# driver.net
KiCad netlist of a schematic drawn in Altium Designer
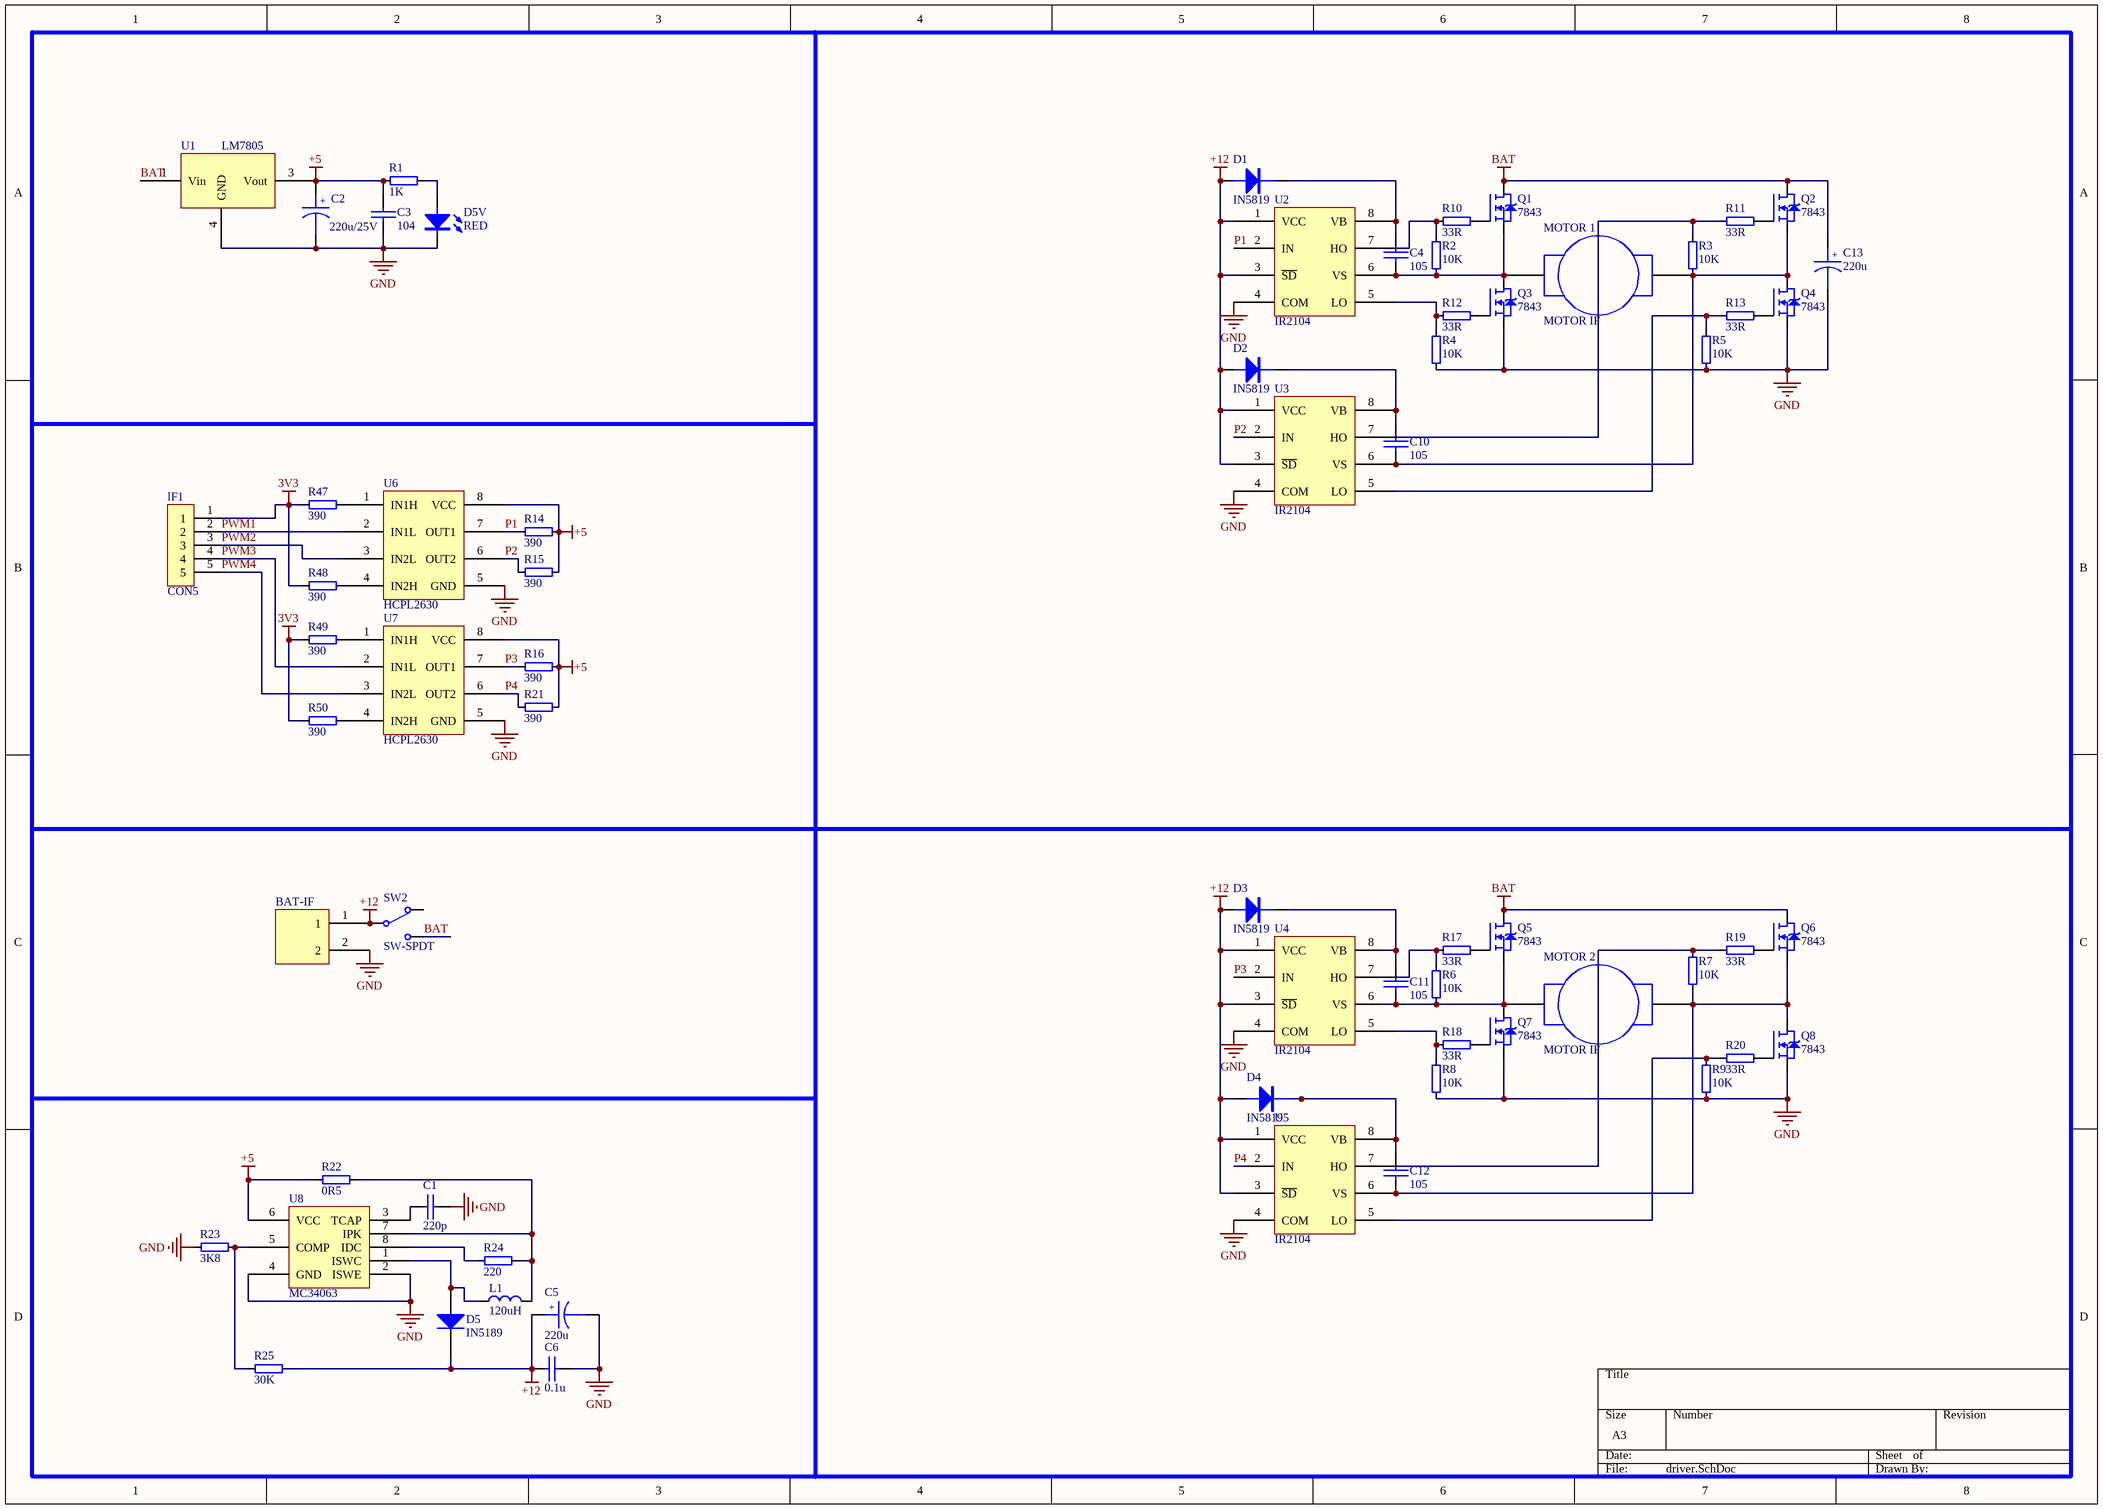
[diagram p0: driver.SchDoc]

(export (version "E")
  (design (tool "Eeschema 10.0.6"))
  (components
    (comp (ref "B1") (value "BAT-IF") (footprint "KF301-2P") (libsource (lib "General") (part "BAT-IF")))
    (comp (ref "C1")
      (value "220p")
      (footprint "0603")
      (description "Capacitor")
      (libsource (lib "电容") (part "普通电容"))
    )
    (comp (ref "C2")
      (value "220u/25V")
      (footprint "CAP 2.5*6.3*7 - BK")
      (description "Capacitor")
      (libsource (lib "电容") (part "电解电容"))
    )
    (comp (ref "C3")
      (value "104")
      (footprint "0603")
      (description "Capacitor")
      (libsource (lib "电容") (part "普通电容"))
    )
    (comp (ref "C4")
      (value "105")
      (footprint "0603")
      (description "Capacitor")
      (libsource (lib "电容") (part "普通电容"))
    )
    (comp (ref "C5")
      (value "220u")
      (footprint "CAP 2.5*6.3*7 - BK")
      (description "Capacitor")
      (libsource (lib "电容") (part "电解电容"))
    )
    (comp (ref "C6")
      (value "0.1u")
      (footprint "0603")
      (description "Capacitor")
      (libsource (lib "电容") (part "普通电容"))
    )
    (comp (ref "C10")
      (value "105")
      (footprint "0603")
      (description "Capacitor")
      (libsource (lib "电容") (part "普通电容"))
    )
    (comp (ref "C11")
      (value "105")
      (footprint "0603")
      (description "Capacitor")
      (libsource (lib "电容") (part "普通电容"))
    )
    (comp (ref "C12")
      (value "105")
      (footprint "0603")
      (description "Capacitor")
      (libsource (lib "电容") (part "普通电容"))
    )
    (comp (ref "C13")
      (value "220u")
      (footprint "CAP 2.5*6.3*7 - BK")
      (description "Capacitor")
      (libsource (lib "电容") (part "电解电容"))
    )
    (comp (ref "D1") (value "IN5819") (footprint "SOD-123") (libsource (lib "常用1") (part "DIODE")))
    (comp (ref "D2") (value "IN5819") (footprint "SOD-123") (libsource (lib "常用1") (part "DIODE")))
    (comp (ref "D3") (value "IN5819") (footprint "SOD-123") (libsource (lib "常用1") (part "DIODE")))
    (comp (ref "D4") (value "IN5819") (footprint "SOD-123") (libsource (lib "常用1") (part "DIODE")))
    (comp (ref "D5")
      (value "IN5189")
      (footprint "SMA")
      (description "SS14")
      (fields (field (name "PUBLISHER") "Altium Limited"))
      (libsource (lib "Miscellaneous Devices") (part "Diode 1N5400"))
    )
    (comp (ref "D5V")
      (value "RED")
      (footprint "LED-0603")
      (description "LED")
      (libsource (lib "General") (part "LED"))
    )
    (comp (ref "L1")
      (value "120uH")
      (footprint "L1210")
      (description "Inductance")
      (libsource (lib "General") (part "INDUCTANCE"))
    )
    (comp (ref "lF1") (value "CON5") (footprint "2.54排针1X5") (libsource (lib "常用元件库") (part "CON5")))
    (comp (ref "MOTOR 1")
      (value "MOTOR IF")
      (footprint "KF301-2P")
      (libsource (lib "General") (part "MOTOR IF"))
    )
    (comp (ref "MOTOR 2")
      (value "MOTOR IF")
      (footprint "KF301-2P")
      (libsource (lib "General") (part "MOTOR IF"))
    )
    (comp (ref "Q1")
      (value "7843")
      (footprint "TO-252")
      (description "N-Channel MOSFET")
      (libsource (lib "General") (part "FDB52N20_2"))
    )
    (comp (ref "Q2")
      (value "7843")
      (footprint "TO-252")
      (description "N-Channel MOSFET")
      (libsource (lib "General") (part "FDB52N20_2"))
    )
    (comp (ref "Q3")
      (value "7843")
      (footprint "TO-252")
      (description "N-Channel MOSFET")
      (libsource (lib "General") (part "FDB52N20_2"))
    )
    (comp (ref "Q4")
      (value "7843")
      (footprint "TO-252")
      (description "N-Channel MOSFET")
      (libsource (lib "General") (part "FDB52N20_2"))
    )
    (comp (ref "Q5")
      (value "7843")
      (footprint "TO-252")
      (description "N-Channel MOSFET")
      (libsource (lib "General") (part "FDB52N20_2"))
    )
    (comp (ref "Q6")
      (value "7843")
      (footprint "TO-252")
      (description "N-Channel MOSFET")
      (libsource (lib "General") (part "FDB52N20_2"))
    )
    (comp (ref "Q7")
      (value "7843")
      (footprint "TO-252")
      (description "N-Channel MOSFET")
      (libsource (lib "General") (part "FDB52N20_2"))
    )
    (comp (ref "Q8")
      (value "7843")
      (footprint "TO-252")
      (description "N-Channel MOSFET")
      (libsource (lib "General") (part "FDB52N20_2"))
    )
    (comp (ref "R1") (value "1K") (footprint "0603") (libsource (lib "电阻") (part "RES")))
    (comp (ref "R2") (value "10K") (footprint "0603") (libsource (lib "电阻") (part "RES")))
    (comp (ref "R3") (value "10K") (footprint "0603") (libsource (lib "电阻") (part "RES")))
    (comp (ref "R4") (value "10K") (footprint "0603") (libsource (lib "电阻") (part "RES")))
    (comp (ref "R5") (value "10K") (footprint "0603") (libsource (lib "电阻") (part "RES")))
    (comp (ref "R6") (value "10K") (footprint "0603") (libsource (lib "电阻") (part "RES")))
    (comp (ref "R7") (value "10K") (footprint "0603") (libsource (lib "电阻") (part "RES")))
    (comp (ref "R8") (value "10K") (footprint "0603") (libsource (lib "电阻") (part "RES")))
    (comp (ref "R9") (value "10K") (footprint "0603") (libsource (lib "电阻") (part "RES")))
    (comp (ref "R10") (value "33R") (footprint "0603") (libsource (lib "电阻") (part "RES")))
    (comp (ref "R11") (value "33R") (footprint "0603") (libsource (lib "电阻") (part "RES")))
    (comp (ref "R12") (value "33R") (footprint "0603") (libsource (lib "电阻") (part "RES")))
    (comp (ref "R13") (value "33R") (footprint "0603") (libsource (lib "电阻") (part "RES")))
    (comp (ref "R14") (value "390") (footprint "0603") (libsource (lib "电阻") (part "RES")))
    (comp (ref "R15") (value "390") (footprint "0603") (libsource (lib "电阻") (part "RES")))
    (comp (ref "R16") (value "390") (footprint "0603") (libsource (lib "电阻") (part "RES")))
    (comp (ref "R17") (value "33R") (footprint "0603") (libsource (lib "电阻") (part "RES")))
    (comp (ref "R18") (value "33R") (footprint "0603") (libsource (lib "电阻") (part "RES")))
    (comp (ref "R19") (value "33R") (footprint "0603") (libsource (lib "电阻") (part "RES")))
    (comp (ref "R20") (value "33R") (footprint "0603") (libsource (lib "电阻") (part "RES")))
    (comp (ref "R21") (value "390") (footprint "0603") (libsource (lib "电阻") (part "RES")))
    (comp (ref "R22") (value "0R5") (footprint "0603") (libsource (lib "电阻") (part "RES")))
    (comp (ref "R23") (value "3K8") (footprint "0603") (libsource (lib "电阻") (part "RES")))
    (comp (ref "R24") (value "220") (footprint "0603") (libsource (lib "电阻") (part "RES")))
    (comp (ref "R25") (value "30K") (footprint "0603") (libsource (lib "电阻") (part "RES")))
    (comp (ref "R47") (value "390") (footprint "0603") (libsource (lib "电阻") (part "RES")))
    (comp (ref "R48") (value "390") (footprint "0603") (libsource (lib "电阻") (part "RES")))
    (comp (ref "R49") (value "390") (footprint "0603") (libsource (lib "电阻") (part "RES")))
    (comp (ref "R50") (value "390") (footprint "0603") (libsource (lib "电阻") (part "RES")))
    (comp (ref "SW2")
      (value "SW-SPDT")
      (footprint "SW3-H2X3_8.6X4.5_L")
      (description "Switch")
      (libsource (lib "General") (part "SWITCH-NKK-M201x"))
    )
    (comp (ref "U1") (value "LM7805") (footprint "TO-252") (libsource (lib "电源") (part "7805")))
    (comp (ref "U2") (value "IR2104") (footprint "SO8_M") (libsource (lib "General") (part "IR2104")))
    (comp (ref "U3") (value "IR2104") (footprint "SO8_M") (libsource (lib "General") (part "IR2104")))
    (comp (ref "U4") (value "IR2104") (footprint "SO8_M") (libsource (lib "General") (part "IR2104")))
    (comp (ref "U5") (value "IR2104") (footprint "SO8_M") (libsource (lib "General") (part "IR2104")))
    (comp (ref "U6") (value "HCPL2630") (footprint "DIP-8") (libsource (lib "常用元件库") (part "HCPL2630")))
    (comp (ref "U7") (value "HCPL2630") (footprint "DIP-8") (libsource (lib "常用元件库") (part "HCPL2630")))
    (comp (ref "U8") (value "MC34063") (footprint "SO-8") (libsource (lib "PCB_Project") (part "MC34063")))
  )
  (nets
    (net (code "1") (name "+5") (class "Default")
      (node (ref "C2") (pin "1") (pinfunction "1_1") (pintype "passive"))
      (node (ref "C3") (pin "1") (pinfunction "1_1") (pintype "passive"))
      (node (ref "R1") (pin "1") (pinfunction "1_1") (pintype "passive"))
      (node (ref "R14") (pin "1") (pinfunction "1_1") (pintype "passive"))
      (node (ref "R15") (pin "1") (pinfunction "1_1") (pintype "passive"))
      (node (ref "R16") (pin "2") (pinfunction "2_2") (pintype "passive"))
      (node (ref "R21") (pin "1") (pinfunction "1_1") (pintype "passive"))
      (node (ref "R22") (pin "1") (pinfunction "1_1") (pintype "passive"))
      (node (ref "U1") (pin "3") (pinfunction "Vout_3") (pintype "passive"))
      (node (ref "U6") (pin "8") (pinfunction "VCC_8") (pintype "passive"))
      (node (ref "U7") (pin "8") (pinfunction "VCC_8") (pintype "passive"))
      (node (ref "U8") (pin "6") (pinfunction "VCC_6") (pintype "passive"))
    )
    (net (code "2") (name "+12") (class "Default")
      (node (ref "B1") (pin "1") (pinfunction "1_1") (pintype "passive"))
      (node (ref "C5") (pin "1") (pinfunction "1_1") (pintype "passive"))
      (node (ref "C6") (pin "1") (pinfunction "1_1") (pintype "passive"))
      (node (ref "D1") (pin "1") (pintype "passive"))
      (node (ref "D2") (pin "1") (pintype "passive"))
      (node (ref "D3") (pin "1") (pintype "passive"))
      (node (ref "D4") (pin "1") (pintype "passive"))
      (node (ref "D5") (pin "2") (pinfunction "K_2") (pintype "passive"))
      (node (ref "R25") (pin "2") (pinfunction "2_2") (pintype "passive"))
      (node (ref "SW2") (pin "2") (pinfunction "2_2") (pintype "passive"))
      (node (ref "U2") (pin "1") (pinfunction "VCC_1") (pintype "passive"))
      (node (ref "U2") (pin "3") (pinfunction "~{SD}_3") (pintype "passive"))
      (node (ref "U3") (pin "1") (pinfunction "VCC_1") (pintype "passive"))
      (node (ref "U3") (pin "3") (pinfunction "~{SD}_3") (pintype "passive"))
      (node (ref "U4") (pin "1") (pinfunction "VCC_1") (pintype "passive"))
      (node (ref "U4") (pin "3") (pinfunction "~{SD}_3") (pintype "passive"))
      (node (ref "U5") (pin "1") (pinfunction "VCC_1") (pintype "passive"))
      (node (ref "U5") (pin "3") (pinfunction "~{SD}_3") (pintype "passive"))
    )
    (net (code "3") (name "/P1") (class "Default")
      (node (ref "R14") (pin "2") (pinfunction "2_2") (pintype "passive"))
      (node (ref "U2") (pin "2") (pinfunction "IN_2") (pintype "passive"))
      (node (ref "U6") (pin "7") (pinfunction "OUT1_7") (pintype "passive"))
    )
    (net (code "4") (name "/P2") (class "Default")
      (node (ref "R15") (pin "2") (pinfunction "2_2") (pintype "passive"))
      (node (ref "U3") (pin "2") (pinfunction "IN_2") (pintype "passive"))
      (node (ref "U6") (pin "6") (pinfunction "OUT2_6") (pintype "passive"))
    )
    (net (code "5") (name "/P3") (class "Default")
      (node (ref "R16") (pin "1") (pinfunction "1_1") (pintype "passive"))
      (node (ref "U4") (pin "2") (pinfunction "IN_2") (pintype "passive"))
      (node (ref "U7") (pin "7") (pinfunction "OUT1_7") (pintype "passive"))
    )
    (net (code "6") (name "/P4") (class "Default")
      (node (ref "R21") (pin "2") (pinfunction "2_2") (pintype "passive"))
      (node (ref "U5") (pin "2") (pinfunction "IN_2") (pintype "passive"))
      (node (ref "U7") (pin "6") (pinfunction "OUT2_6") (pintype "passive"))
    )
    (net (code "7") (name "/PWM1") (class "Default")
      (node (ref "U6") (pin "2") (pinfunction "IN1L_2") (pintype "passive"))
      (node (ref "lF1") (pin "2") (pinfunction "2_2") (pintype "passive"))
    )
    (net (code "8") (name "/PWM2") (class "Default")
      (node (ref "U6") (pin "3") (pinfunction "IN2L_3") (pintype "passive"))
      (node (ref "lF1") (pin "3") (pinfunction "3_3") (pintype "passive"))
    )
    (net (code "9") (name "/PWM3") (class "Default")
      (node (ref "U7") (pin "2") (pinfunction "IN1L_2") (pintype "passive"))
      (node (ref "lF1") (pin "4") (pinfunction "4_4") (pintype "passive"))
    )
    (net (code "10") (name "/PWM4") (class "Default")
      (node (ref "U7") (pin "3") (pinfunction "IN2L_3") (pintype "passive"))
      (node (ref "lF1") (pin "5") (pinfunction "5_5") (pintype "passive"))
    )
    (net (code "11") (name "3V3") (class "Default")
      (node (ref "R47") (pin "1") (pinfunction "1_1") (pintype "passive"))
      (node (ref "R48") (pin "1") (pinfunction "1_1") (pintype "passive"))
      (node (ref "R49") (pin "1") (pinfunction "1_1") (pintype "passive"))
      (node (ref "R50") (pin "1") (pinfunction "1_1") (pintype "passive"))
      (node (ref "lF1") (pin "1") (pinfunction "1_1") (pintype "passive"))
    )
    (net (code "12") (name "BAT") (class "Default")
      (node (ref "C13") (pin "1") (pinfunction "1_1") (pintype "passive"))
      (node (ref "Q1") (pin "4") (pinfunction "D_4") (pintype "passive"))
      (node (ref "Q2") (pin "4") (pinfunction "D_4") (pintype "passive"))
      (node (ref "Q5") (pin "4") (pinfunction "D_4") (pintype "passive"))
      (node (ref "Q6") (pin "4") (pinfunction "D_4") (pintype "passive"))
      (node (ref "SW2") (pin "3") (pinfunction "3_3") (pintype "passive"))
      (node (ref "U1") (pin "1") (pinfunction "Vin_1") (pintype "passive"))
    )
    (net (code "13") (name "GND") (class "Default")
      (node (ref "B1") (pin "2") (pinfunction "2_2") (pintype "passive"))
      (node (ref "C1") (pin "2") (pinfunction "2_2") (pintype "passive"))
      (node (ref "C13") (pin "2") (pinfunction "2_2") (pintype "passive"))
      (node (ref "C2") (pin "2") (pinfunction "2_2") (pintype "passive"))
      (node (ref "C3") (pin "2") (pinfunction "2_2") (pintype "passive"))
      (node (ref "C5") (pin "2") (pinfunction "2_2") (pintype "passive"))
      (node (ref "C6") (pin "2") (pinfunction "2_2") (pintype "passive"))
      (node (ref "D5V") (pin "2") (pinfunction "C_2") (pintype "passive"))
      (node (ref "Q3") (pin "3") (pinfunction "S_3") (pintype "passive"))
      (node (ref "Q4") (pin "3") (pinfunction "S_3") (pintype "passive"))
      (node (ref "Q7") (pin "3") (pinfunction "S_3") (pintype "passive"))
      (node (ref "Q8") (pin "3") (pinfunction "S_3") (pintype "passive"))
      (node (ref "R23") (pin "1") (pinfunction "1_1") (pintype "passive"))
      (node (ref "R4") (pin "1") (pinfunction "1_1") (pintype "passive"))
      (node (ref "R5") (pin "1") (pinfunction "1_1") (pintype "passive"))
      (node (ref "R8") (pin "1") (pinfunction "1_1") (pintype "passive"))
      (node (ref "R9") (pin "1") (pinfunction "1_1") (pintype "passive"))
      (node (ref "U1") (pin "4") (pinfunction "GND_4") (pintype "passive"))
      (node (ref "U2") (pin "4") (pinfunction "COM_4") (pintype "passive"))
      (node (ref "U3") (pin "4") (pinfunction "COM_4") (pintype "passive"))
      (node (ref "U4") (pin "4") (pinfunction "COM_4") (pintype "passive"))
      (node (ref "U5") (pin "4") (pinfunction "COM_4") (pintype "passive"))
      (node (ref "U6") (pin "5") (pinfunction "GND_5") (pintype "passive"))
      (node (ref "U7") (pin "5") (pinfunction "GND_5") (pintype "passive"))
      (node (ref "U8") (pin "2") (pinfunction "ISWE_2") (pintype "passive"))
      (node (ref "U8") (pin "4") (pinfunction "GND_4") (pintype "passive"))
    )
    (net (code "14") (name "Net-(D5-A)") (class "Default")
      (node (ref "D5") (pin "1") (pinfunction "A_1") (pintype "passive"))
      (node (ref "L1") (pin "1") (pinfunction "1_1") (pintype "passive"))
      (node (ref "U8") (pin "1") (pinfunction "ISWC_1") (pintype "passive"))
    )
    (net (code "15") (name "Net-(D5V-A)") (class "Default")
      (node (ref "D5V") (pin "1") (pinfunction "A_1") (pintype "passive"))
      (node (ref "R1") (pin "2") (pinfunction "2_2") (pintype "passive"))
    )
    (net (code "16") (name "Net-(Q1-G)") (class "Default")
      (node (ref "Q1") (pin "1") (pinfunction "G_1") (pintype "passive"))
      (node (ref "R10") (pin "2") (pinfunction "2_2") (pintype "passive"))
    )
    (net (code "17") (name "Net-(Q1-S)") (class "Default")
      (node (ref "C4") (pin "2") (pinfunction "2_2") (pintype "passive"))
      (node (ref "MOTOR 1") (pin "2") (pinfunction "2_2") (pintype "passive"))
      (node (ref "Q1") (pin "3") (pinfunction "S_3") (pintype "passive"))
      (node (ref "Q3") (pin "4") (pinfunction "D_4") (pintype "passive"))
      (node (ref "R2") (pin "1") (pinfunction "1_1") (pintype "passive"))
      (node (ref "U2") (pin "6") (pinfunction "VS_6") (pintype "passive"))
    )
    (net (code "18") (name "Net-(Q2-G)") (class "Default")
      (node (ref "Q2") (pin "1") (pinfunction "G_1") (pintype "passive"))
      (node (ref "R11") (pin "2") (pinfunction "2_2") (pintype "passive"))
    )
    (net (code "19") (name "Net-(Q2-S)") (class "Default")
      (node (ref "C10") (pin "2") (pinfunction "2_2") (pintype "passive"))
      (node (ref "MOTOR 1") (pin "1") (pinfunction "1_1") (pintype "passive"))
      (node (ref "Q2") (pin "3") (pinfunction "S_3") (pintype "passive"))
      (node (ref "Q4") (pin "4") (pinfunction "D_4") (pintype "passive"))
      (node (ref "R3") (pin "1") (pinfunction "1_1") (pintype "passive"))
      (node (ref "U3") (pin "6") (pinfunction "VS_6") (pintype "passive"))
    )
    (net (code "20") (name "Net-(Q3-G)") (class "Default")
      (node (ref "Q3") (pin "1") (pinfunction "G_1") (pintype "passive"))
      (node (ref "R12") (pin "2") (pinfunction "2_2") (pintype "passive"))
    )
    (net (code "21") (name "Net-(Q4-G)") (class "Default")
      (node (ref "Q4") (pin "1") (pinfunction "G_1") (pintype "passive"))
      (node (ref "R13") (pin "2") (pinfunction "2_2") (pintype "passive"))
    )
    (net (code "22") (name "Net-(Q5-G)") (class "Default")
      (node (ref "Q5") (pin "1") (pinfunction "G_1") (pintype "passive"))
      (node (ref "R17") (pin "2") (pinfunction "2_2") (pintype "passive"))
    )
    (net (code "23") (name "Net-(Q5-S)") (class "Default")
      (node (ref "C11") (pin "2") (pinfunction "2_2") (pintype "passive"))
      (node (ref "MOTOR 2") (pin "2") (pinfunction "2_2") (pintype "passive"))
      (node (ref "Q5") (pin "3") (pinfunction "S_3") (pintype "passive"))
      (node (ref "Q7") (pin "4") (pinfunction "D_4") (pintype "passive"))
      (node (ref "R6") (pin "1") (pinfunction "1_1") (pintype "passive"))
      (node (ref "U4") (pin "6") (pinfunction "VS_6") (pintype "passive"))
    )
    (net (code "24") (name "Net-(Q6-G)") (class "Default")
      (node (ref "Q6") (pin "1") (pinfunction "G_1") (pintype "passive"))
      (node (ref "R19") (pin "2") (pinfunction "2_2") (pintype "passive"))
    )
    (net (code "25") (name "Net-(Q6-S)") (class "Default")
      (node (ref "C12") (pin "2") (pinfunction "2_2") (pintype "passive"))
      (node (ref "MOTOR 2") (pin "1") (pinfunction "1_1") (pintype "passive"))
      (node (ref "Q6") (pin "3") (pinfunction "S_3") (pintype "passive"))
      (node (ref "Q8") (pin "4") (pinfunction "D_4") (pintype "passive"))
      (node (ref "R7") (pin "1") (pinfunction "1_1") (pintype "passive"))
      (node (ref "U5") (pin "6") (pinfunction "VS_6") (pintype "passive"))
    )
    (net (code "26") (name "Net-(Q7-G)") (class "Default")
      (node (ref "Q7") (pin "1") (pinfunction "G_1") (pintype "passive"))
      (node (ref "R18") (pin "2") (pinfunction "2_2") (pintype "passive"))
    )
    (net (code "27") (name "Net-(Q8-G)") (class "Default")
      (node (ref "Q8") (pin "1") (pinfunction "G_1") (pintype "passive"))
      (node (ref "R20") (pin "2") (pinfunction "2_2") (pintype "passive"))
    )
    (net (code "28") (name "Net-(U2-HO)") (class "Default")
      (node (ref "R10") (pin "1") (pinfunction "1_1") (pintype "passive"))
      (node (ref "R2") (pin "2") (pinfunction "2_2") (pintype "passive"))
      (node (ref "U2") (pin "7") (pinfunction "HO_7") (pintype "passive"))
    )
    (net (code "29") (name "Net-(U2-LO)") (class "Default")
      (node (ref "R12") (pin "1") (pinfunction "1_1") (pintype "passive"))
      (node (ref "R4") (pin "2") (pinfunction "2_2") (pintype "passive"))
      (node (ref "U2") (pin "5") (pinfunction "LO_5") (pintype "passive"))
    )
    (net (code "30") (name "Net-(U2-VB)") (class "Default")
      (node (ref "C4") (pin "1") (pinfunction "1_1") (pintype "passive"))
      (node (ref "D1") (pin "2") (pintype "passive"))
      (node (ref "U2") (pin "8") (pinfunction "VB_8") (pintype "passive"))
    )
    (net (code "31") (name "Net-(U3-HO)") (class "Default")
      (node (ref "R11") (pin "1") (pinfunction "1_1") (pintype "passive"))
      (node (ref "R3") (pin "2") (pinfunction "2_2") (pintype "passive"))
      (node (ref "U3") (pin "7") (pinfunction "HO_7") (pintype "passive"))
    )
    (net (code "32") (name "Net-(U3-LO)") (class "Default")
      (node (ref "R13") (pin "1") (pinfunction "1_1") (pintype "passive"))
      (node (ref "R5") (pin "2") (pinfunction "2_2") (pintype "passive"))
      (node (ref "U3") (pin "5") (pinfunction "LO_5") (pintype "passive"))
    )
    (net (code "33") (name "Net-(U3-VB)") (class "Default")
      (node (ref "C10") (pin "1") (pinfunction "1_1") (pintype "passive"))
      (node (ref "D2") (pin "2") (pintype "passive"))
      (node (ref "U3") (pin "8") (pinfunction "VB_8") (pintype "passive"))
    )
    (net (code "34") (name "Net-(U4-HO)") (class "Default")
      (node (ref "R17") (pin "1") (pinfunction "1_1") (pintype "passive"))
      (node (ref "R6") (pin "2") (pinfunction "2_2") (pintype "passive"))
      (node (ref "U4") (pin "7") (pinfunction "HO_7") (pintype "passive"))
    )
    (net (code "35") (name "Net-(U4-LO)") (class "Default")
      (node (ref "R18") (pin "1") (pinfunction "1_1") (pintype "passive"))
      (node (ref "R8") (pin "2") (pinfunction "2_2") (pintype "passive"))
      (node (ref "U4") (pin "5") (pinfunction "LO_5") (pintype "passive"))
    )
    (net (code "36") (name "Net-(U4-VB)") (class "Default")
      (node (ref "C11") (pin "1") (pinfunction "1_1") (pintype "passive"))
      (node (ref "D3") (pin "2") (pintype "passive"))
      (node (ref "U4") (pin "8") (pinfunction "VB_8") (pintype "passive"))
    )
    (net (code "37") (name "Net-(U5-HO)") (class "Default")
      (node (ref "R19") (pin "1") (pinfunction "1_1") (pintype "passive"))
      (node (ref "R7") (pin "2") (pinfunction "2_2") (pintype "passive"))
      (node (ref "U5") (pin "7") (pinfunction "HO_7") (pintype "passive"))
    )
    (net (code "38") (name "Net-(U5-LO)") (class "Default")
      (node (ref "R20") (pin "1") (pinfunction "1_1") (pintype "passive"))
      (node (ref "R9") (pin "2") (pinfunction "2_2") (pintype "passive"))
      (node (ref "U5") (pin "5") (pinfunction "LO_5") (pintype "passive"))
    )
    (net (code "39") (name "Net-(U5-VB)") (class "Default")
      (node (ref "C12") (pin "1") (pinfunction "1_1") (pintype "passive"))
      (node (ref "D4") (pin "2") (pintype "passive"))
      (node (ref "U5") (pin "8") (pinfunction "VB_8") (pintype "passive"))
    )
    (net (code "40") (name "Net-(U6-IN1H)") (class "Default")
      (node (ref "R47") (pin "2") (pinfunction "2_2") (pintype "passive"))
      (node (ref "U6") (pin "1") (pinfunction "IN1H_1") (pintype "passive"))
    )
    (net (code "41") (name "Net-(U6-IN2H)") (class "Default")
      (node (ref "R48") (pin "2") (pinfunction "2_2") (pintype "passive"))
      (node (ref "U6") (pin "4") (pinfunction "IN2H_4") (pintype "passive"))
    )
    (net (code "42") (name "Net-(U7-IN1H)") (class "Default")
      (node (ref "R49") (pin "2") (pinfunction "2_2") (pintype "passive"))
      (node (ref "U7") (pin "1") (pinfunction "IN1H_1") (pintype "passive"))
    )
    (net (code "43") (name "Net-(U7-IN2H)") (class "Default")
      (node (ref "R50") (pin "2") (pinfunction "2_2") (pintype "passive"))
      (node (ref "U7") (pin "4") (pinfunction "IN2H_4") (pintype "passive"))
    )
    (net (code "44") (name "Net-(U8-COMP)") (class "Default")
      (node (ref "R23") (pin "2") (pinfunction "2_2") (pintype "passive"))
      (node (ref "R25") (pin "1") (pinfunction "1_1") (pintype "passive"))
      (node (ref "U8") (pin "5") (pinfunction "COMP_5") (pintype "passive"))
    )
    (net (code "45") (name "Net-(U8-IDC)") (class "Default")
      (node (ref "R24") (pin "1") (pinfunction "1_1") (pintype "passive"))
      (node (ref "U8") (pin "8") (pinfunction "IDC_8") (pintype "passive"))
    )
    (net (code "46") (name "Net-(U8-IPK)") (class "Default")
      (node (ref "L1") (pin "2") (pinfunction "2_2") (pintype "passive"))
      (node (ref "R22") (pin "2") (pinfunction "2_2") (pintype "passive"))
      (node (ref "R24") (pin "2") (pinfunction "2_2") (pintype "passive"))
      (node (ref "U8") (pin "7") (pinfunction "IPK_7") (pintype "passive"))
    )
    (net (code "47") (name "Net-(U8-TCAP)") (class "Default")
      (node (ref "C1") (pin "1") (pinfunction "1_1") (pintype "passive"))
      (node (ref "U8") (pin "3") (pinfunction "TCAP_3") (pintype "passive"))
    )
    (net (code "48") (name "unconnected-(SW2-Pad1)") (class "Default")
      (node (ref "SW2") (pin "1") (pinfunction "1_1") (pintype "passive"))
    )
  )
)
